# Komponenta.net
KiCad netlist of a schematic drawn in Altium Designer
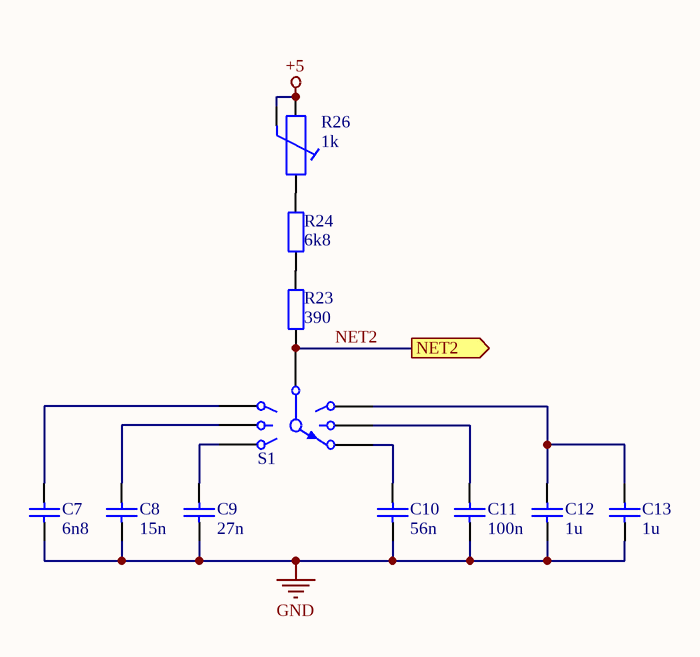
[diagram p0: Komponenta.SchDoc]

(export (version "E")
  (design (tool "Eeschema 10.0.6"))
  (components
    (comp (ref "C7")
      (value "6n8")
      (footprint "RAD-0.3")
      (description "Capacitor")
      (fields (field (name "PUBLISHER") "Altium Limited"))
      (libsource (lib "Miscellaneous Devices") (part "Cap"))
    )
    (comp (ref "C8")
      (value "15n")
      (footprint "RAD-0.3")
      (description "Capacitor")
      (fields (field (name "PUBLISHER") "Altium Limited"))
      (libsource (lib "Miscellaneous Devices") (part "Cap"))
    )
    (comp (ref "C9")
      (value "27n")
      (footprint "RAD-0.3")
      (description "Capacitor")
      (fields (field (name "PUBLISHER") "Altium Limited"))
      (libsource (lib "Miscellaneous Devices") (part "Cap"))
    )
    (comp (ref "C10")
      (value "56n")
      (footprint "RAD-0.3")
      (description "Capacitor")
      (fields (field (name "PUBLISHER") "Altium Limited"))
      (libsource (lib "Miscellaneous Devices") (part "Cap"))
    )
    (comp (ref "C11")
      (value "100n")
      (footprint "RAD-0.3")
      (description "Capacitor")
      (fields (field (name "PUBLISHER") "Altium Limited"))
      (libsource (lib "Miscellaneous Devices") (part "Cap"))
    )
    (comp (ref "C12")
      (value "1u")
      (footprint "RAD-0.3")
      (description "Capacitor")
      (fields (field (name "PUBLISHER") "Altium Limited"))
      (libsource (lib "Miscellaneous Devices") (part "Cap"))
    )
    (comp (ref "C13")
      (value "1u")
      (footprint "RAD-0.3")
      (description "Capacitor")
      (fields (field (name "PUBLISHER") "Altium Limited"))
      (libsource (lib "Miscellaneous Devices") (part "Cap"))
    )
    (comp (ref "R23")
      (value "390")
      (footprint "AXIAL-0.4")
      (description "Resistor")
      (fields (field (name "PUBLISHER") "Altium Limited"))
      (libsource (lib "Miscellaneous Devices") (part "Res2"))
    )
    (comp (ref "R24")
      (value "6k8")
      (footprint "AXIAL-0.4")
      (description "Resistor")
      (fields (field (name "PUBLISHER") "Altium Limited"))
      (libsource (lib "Miscellaneous Devices") (part "Res2"))
    )
    (comp (ref "R26") (value "1k") (footprint "6-0805_N") (libsource (lib "Indikator_lib") (part "Trimmer")))
    (comp (ref "S1")
      (value "SW-6WAY")
      (footprint "SW-7")
      (description "6 Way Switch")
      (fields (field (name "PUBLISHER") "Altium Limited"))
      (libsource (lib "Miscellaneous Devices") (part "SW-6WAY"))
    )
  )
  (nets
    (net (code "1") (name "+5") (class "Default")
      (node (ref "R26") (pin "1") (pinfunction "1_1") (pintype "passive"))
      (node (ref "R26") (pin "2") (pinfunction "2_2") (pintype "passive"))
    )
    (net (code "2") (name "/NET2") (class "Default")
      (node (ref "R23") (pin "2") (pinfunction "2_2") (pintype "passive"))
      (node (ref "S1") (pin "7") (pinfunction "7_7") (pintype "passive"))
    )
    (net (code "3") (name "GND") (class "Default")
      (node (ref "C10") (pin "1") (pinfunction "1_1") (pintype "passive"))
      (node (ref "C11") (pin "1") (pinfunction "1_1") (pintype "passive"))
      (node (ref "C12") (pin "1") (pinfunction "1_1") (pintype "passive"))
      (node (ref "C13") (pin "1") (pinfunction "1_1") (pintype "passive"))
      (node (ref "C7") (pin "1") (pinfunction "1_1") (pintype "passive"))
      (node (ref "C8") (pin "1") (pinfunction "1_1") (pintype "passive"))
      (node (ref "C9") (pin "1") (pinfunction "1_1") (pintype "passive"))
    )
    (net (code "4") (name "Net-(C7-Pad2)") (class "Default")
      (node (ref "C7") (pin "2") (pinfunction "2_2") (pintype "passive"))
      (node (ref "S1") (pin "1") (pinfunction "1_1") (pintype "passive"))
    )
    (net (code "5") (name "Net-(C8-Pad2)") (class "Default")
      (node (ref "C8") (pin "2") (pinfunction "2_2") (pintype "passive"))
      (node (ref "S1") (pin "2") (pinfunction "2_2") (pintype "passive"))
    )
    (net (code "6") (name "Net-(C9-Pad2)") (class "Default")
      (node (ref "C9") (pin "2") (pinfunction "2_2") (pintype "passive"))
      (node (ref "S1") (pin "3") (pinfunction "3_3") (pintype "passive"))
    )
    (net (code "7") (name "Net-(C10-Pad2)") (class "Default")
      (node (ref "C10") (pin "2") (pinfunction "2_2") (pintype "passive"))
      (node (ref "S1") (pin "6") (pinfunction "6_6") (pintype "passive"))
    )
    (net (code "8") (name "Net-(C11-Pad2)") (class "Default")
      (node (ref "C11") (pin "2") (pinfunction "2_2") (pintype "passive"))
      (node (ref "S1") (pin "5") (pinfunction "5_5") (pintype "passive"))
    )
    (net (code "9") (name "Net-(C12-Pad2)") (class "Default")
      (node (ref "C12") (pin "2") (pinfunction "2_2") (pintype "passive"))
      (node (ref "C13") (pin "2") (pinfunction "2_2") (pintype "passive"))
      (node (ref "S1") (pin "4") (pinfunction "4_4") (pintype "passive"))
    )
    (net (code "10") (name "Net-(R23-Pad1)") (class "Default")
      (node (ref "R23") (pin "1") (pinfunction "1_1") (pintype "passive"))
      (node (ref "R24") (pin "2") (pinfunction "2_2") (pintype "passive"))
    )
    (net (code "11") (name "Net-(R24-Pad1)") (class "Default")
      (node (ref "R24") (pin "1") (pinfunction "1_1") (pintype "passive"))
      (node (ref "R26") (pin "0") (pinfunction "0_0") (pintype "passive"))
    )
  )
)
